# Public_QSGMII_ETHERNET.net
KiCad netlist of a schematic drawn in Altium Designer
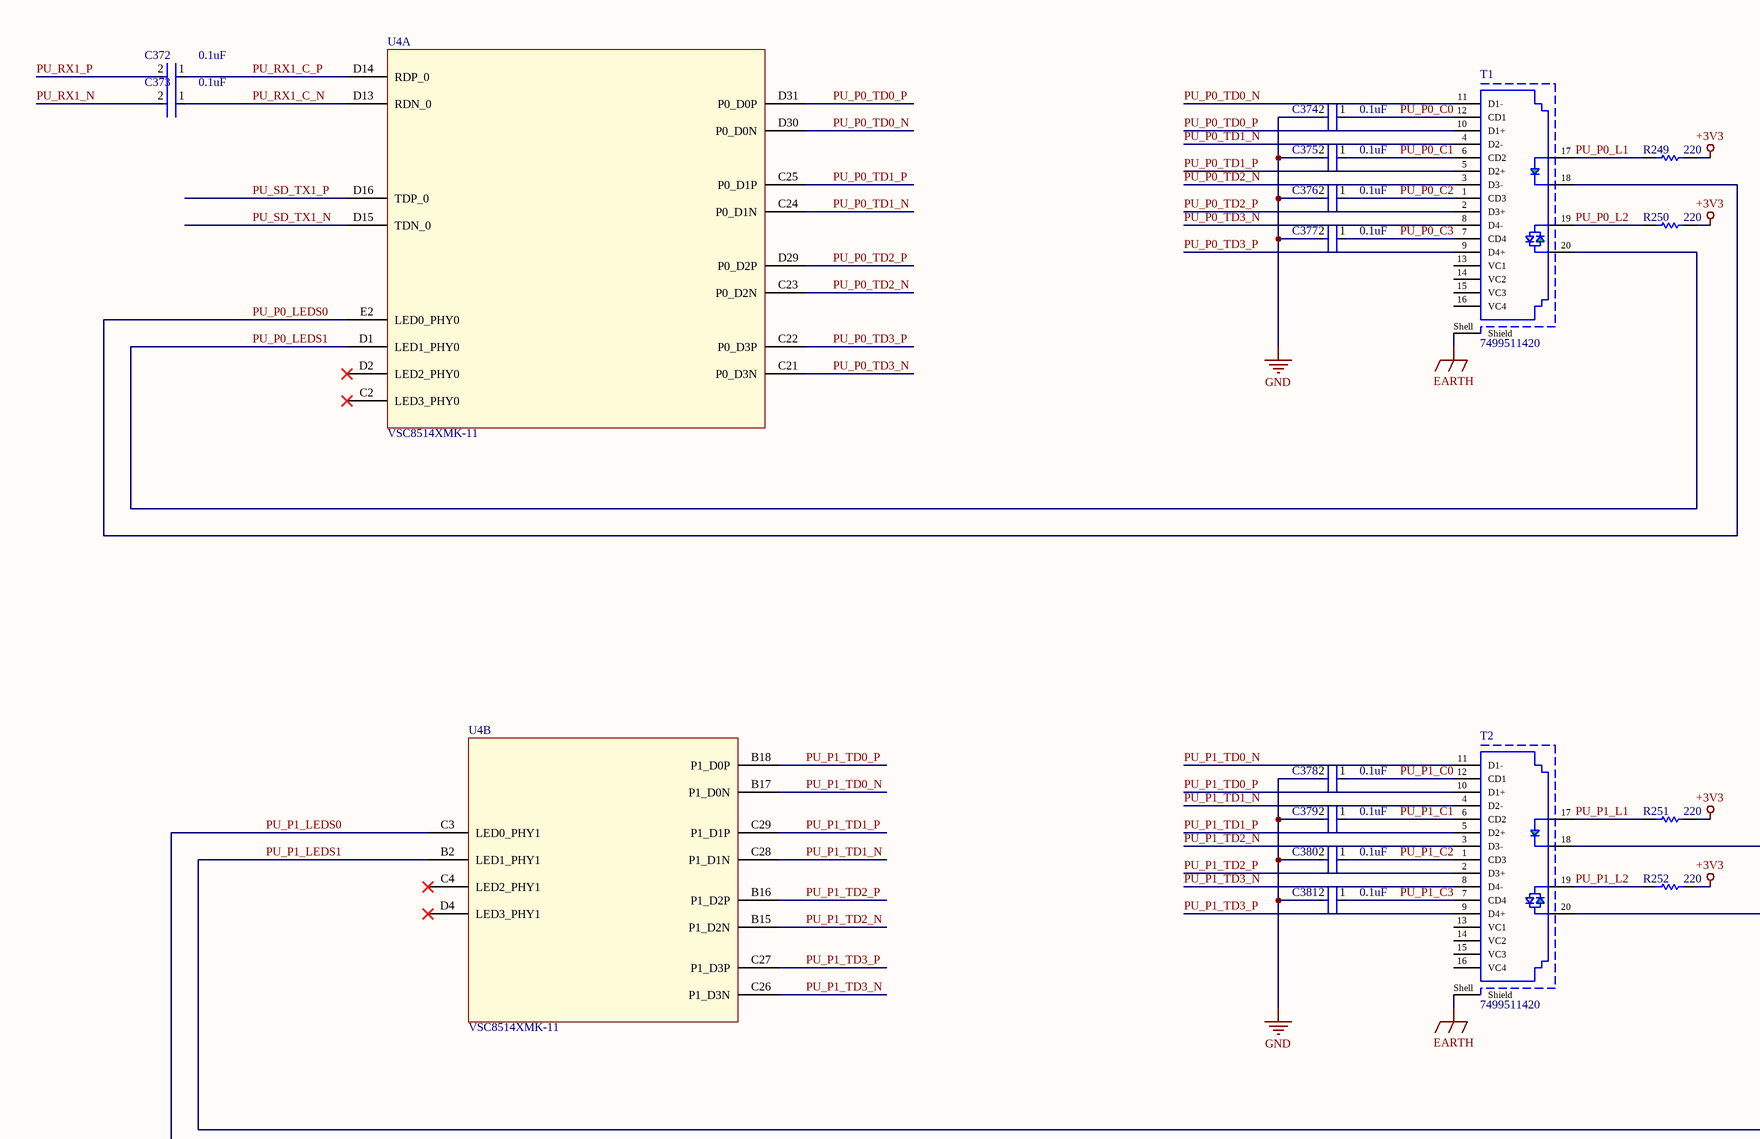
[diagram p0: Public_QSGMII_ETHERNET.SchDoc, top left]
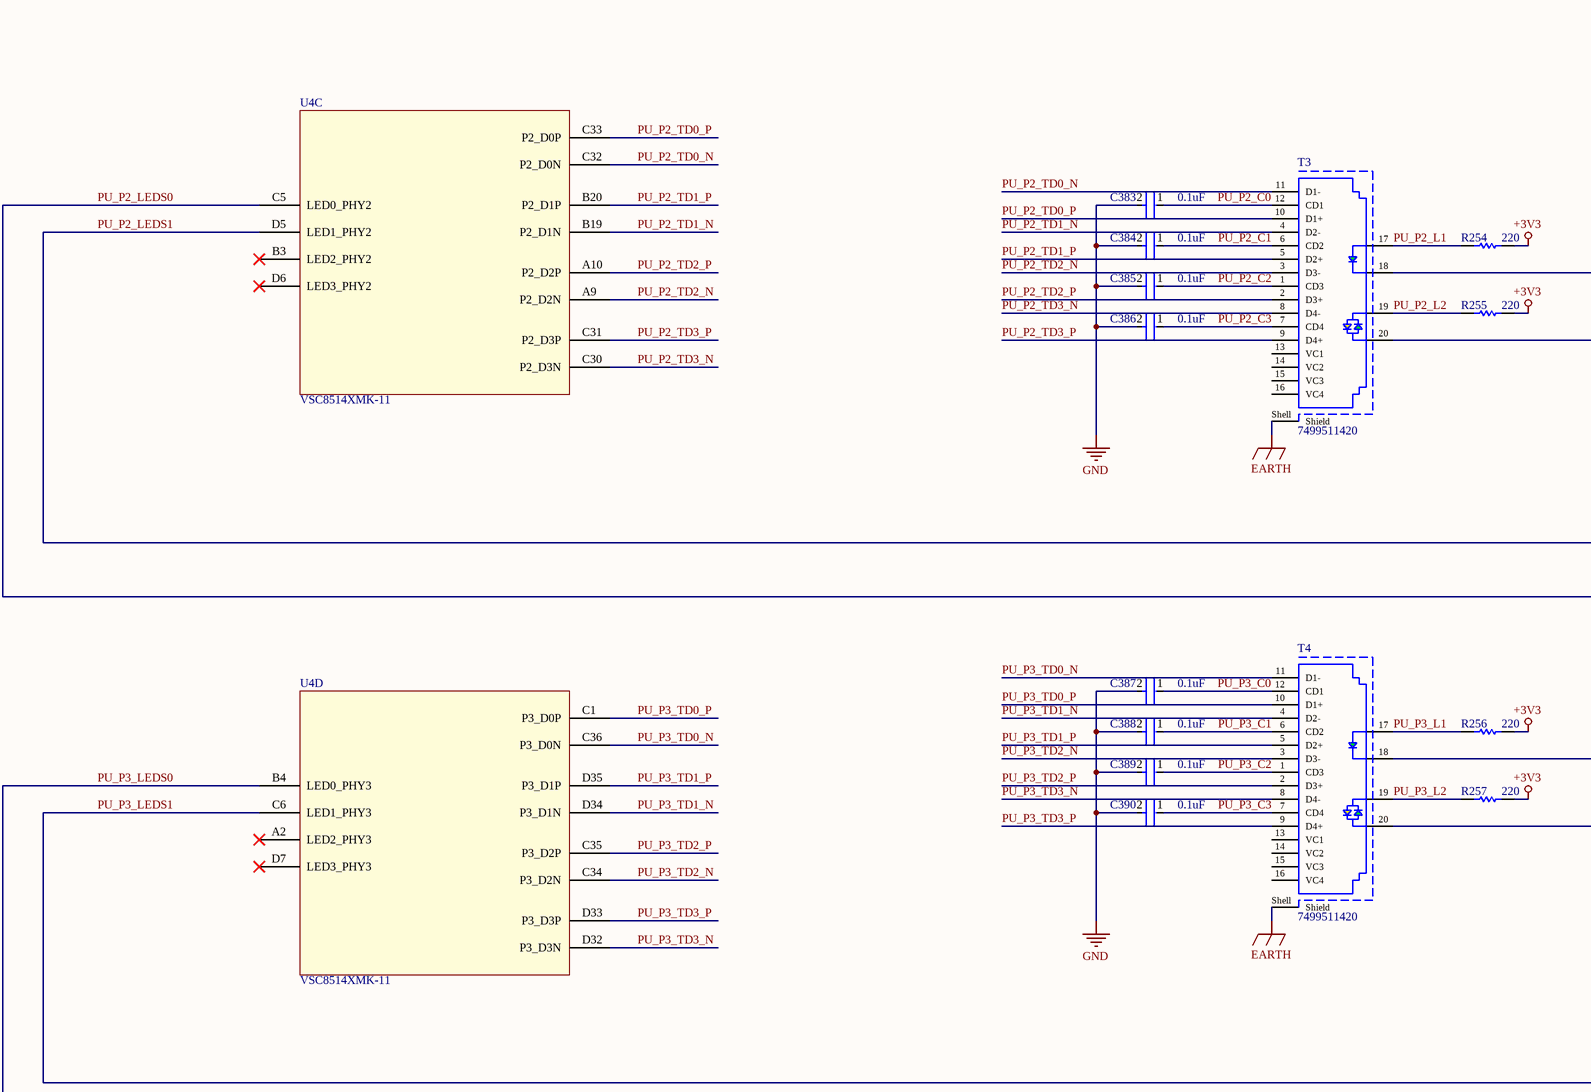
[diagram p1: Public_QSGMII_ETHERNET.SchDoc, bottom left]
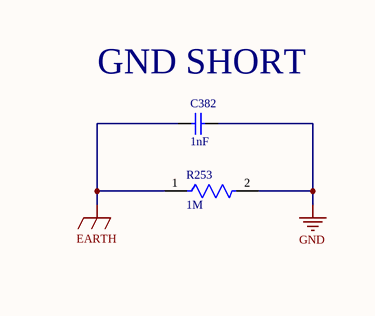
[diagram p2: Public_QSGMII_ETHERNET.SchDoc, bottom right]

(export (version "E")
  (design (tool "Eeschema 10.0.6"))
  (components
    (comp (ref "C372")
      (value "0.1uF")
      (footprint "FP-GRM15-MFG")
      (description "CAP CER 0.1UF 16V X7R 0402")
      (fields (field (name "MANUFACTURER PART NUMBER") "GRM155R71C104KA88D") (field (name "TOLERANCE") "10%"))
      (libsource (lib "Altium Content Vault") (part "236180d848d6139a670b325ea6854c9"))
    )
    (comp (ref "C373")
      (value "0.1uF")
      (footprint "FP-GRM15-MFG")
      (description "CAP CER 0.1UF 16V X7R 0402")
      (fields (field (name "MANUFACTURER PART NUMBER") "GRM155R71C104KA88D") (field (name "TOLERANCE") "10%"))
      (libsource (lib "Altium Content Vault") (part "236180d848d6139a670b325ea6854c9"))
    )
    (comp (ref "C374")
      (value "0.1uF")
      (footprint "FP-GRM15-MFG")
      (description "CAP CER 0.1UF 16V X7R 0402")
      (fields (field (name "MANUFACTURER PART NUMBER") "GRM155R71C104KA88D") (field (name "TOLERANCE") "10%"))
      (libsource (lib "Altium Content Vault") (part "236180d848d6139a670b325ea6854c9"))
    )
    (comp (ref "C375")
      (value "0.1uF")
      (footprint "FP-GRM15-MFG")
      (description "CAP CER 0.1UF 16V X7R 0402")
      (fields (field (name "MANUFACTURER PART NUMBER") "GRM155R71C104KA88D") (field (name "TOLERANCE") "10%"))
      (libsource (lib "Altium Content Vault") (part "236180d848d6139a670b325ea6854c9"))
    )
    (comp (ref "C376")
      (value "0.1uF")
      (footprint "FP-GRM15-MFG")
      (description "CAP CER 0.1UF 16V X7R 0402")
      (fields (field (name "MANUFACTURER PART NUMBER") "GRM155R71C104KA88D") (field (name "TOLERANCE") "10%"))
      (libsource (lib "Altium Content Vault") (part "236180d848d6139a670b325ea6854c9"))
    )
    (comp (ref "C377")
      (value "0.1uF")
      (footprint "FP-GRM15-MFG")
      (description "CAP CER 0.1UF 16V X7R 0402")
      (fields (field (name "MANUFACTURER PART NUMBER") "GRM155R71C104KA88D") (field (name "TOLERANCE") "10%"))
      (libsource (lib "Altium Content Vault") (part "236180d848d6139a670b325ea6854c9"))
    )
    (comp (ref "C378")
      (value "0.1uF")
      (footprint "FP-GRM15-MFG")
      (description "CAP CER 0.1UF 16V X7R 0402")
      (fields (field (name "MANUFACTURER PART NUMBER") "GRM155R71C104KA88D") (field (name "TOLERANCE") "10%"))
      (libsource (lib "Altium Content Vault") (part "236180d848d6139a670b325ea6854c9"))
    )
    (comp (ref "C379")
      (value "0.1uF")
      (footprint "FP-GRM15-MFG")
      (description "CAP CER 0.1UF 16V X7R 0402")
      (fields (field (name "MANUFACTURER PART NUMBER") "GRM155R71C104KA88D") (field (name "TOLERANCE") "10%"))
      (libsource (lib "Altium Content Vault") (part "236180d848d6139a670b325ea6854c9"))
    )
    (comp (ref "C380")
      (value "0.1uF")
      (footprint "FP-GRM15-MFG")
      (description "CAP CER 0.1UF 16V X7R 0402")
      (fields (field (name "MANUFACTURER PART NUMBER") "GRM155R71C104KA88D") (field (name "TOLERANCE") "10%"))
      (libsource (lib "Altium Content Vault") (part "236180d848d6139a670b325ea6854c9"))
    )
    (comp (ref "C381")
      (value "0.1uF")
      (footprint "FP-GRM15-MFG")
      (description "CAP CER 0.1UF 16V X7R 0402")
      (fields (field (name "MANUFACTURER PART NUMBER") "GRM155R71C104KA88D") (field (name "TOLERANCE") "10%"))
      (libsource (lib "Altium Content Vault") (part "236180d848d6139a670b325ea6854c9"))
    )
    (comp (ref "C382")
      (value "1nF")
      (footprint "YAGE-CC1206KKX7R-2_M")
      (description "CAP, Ceramic, 1 nF, 2000 V, 10%, 1206, RoHS, Tape and Reel")
      (fields (field (name "MANUFACTURER") "Yageo") (field (name "TOLERANCE") "±10%"))
      (libsource (lib "Altium Content Vault") (part "CAP-NP-2"))
    )
    (comp (ref "C383")
      (value "0.1uF")
      (footprint "FP-GRM15-MFG")
      (description "CAP CER 0.1UF 16V X7R 0402")
      (fields (field (name "MANUFACTURER PART NUMBER") "GRM155R71C104KA88D") (field (name "TOLERANCE") "10%"))
      (libsource (lib "Altium Content Vault") (part "236180d848d6139a670b325ea6854c9"))
    )
    (comp (ref "C384")
      (value "0.1uF")
      (footprint "FP-GRM15-MFG")
      (description "CAP CER 0.1UF 16V X7R 0402")
      (fields (field (name "MANUFACTURER PART NUMBER") "GRM155R71C104KA88D") (field (name "TOLERANCE") "10%"))
      (libsource (lib "Altium Content Vault") (part "236180d848d6139a670b325ea6854c9"))
    )
    (comp (ref "C385")
      (value "0.1uF")
      (footprint "FP-GRM15-MFG")
      (description "CAP CER 0.1UF 16V X7R 0402")
      (fields (field (name "MANUFACTURER PART NUMBER") "GRM155R71C104KA88D") (field (name "TOLERANCE") "10%"))
      (libsource (lib "Altium Content Vault") (part "236180d848d6139a670b325ea6854c9"))
    )
    (comp (ref "C386")
      (value "0.1uF")
      (footprint "FP-GRM15-MFG")
      (description "CAP CER 0.1UF 16V X7R 0402")
      (fields (field (name "MANUFACTURER PART NUMBER") "GRM155R71C104KA88D") (field (name "TOLERANCE") "10%"))
      (libsource (lib "Altium Content Vault") (part "236180d848d6139a670b325ea6854c9"))
    )
    (comp (ref "C387")
      (value "0.1uF")
      (footprint "FP-GRM15-MFG")
      (description "CAP CER 0.1UF 16V X7R 0402")
      (fields (field (name "MANUFACTURER PART NUMBER") "GRM155R71C104KA88D") (field (name "TOLERANCE") "10%"))
      (libsource (lib "Altium Content Vault") (part "236180d848d6139a670b325ea6854c9"))
    )
    (comp (ref "C388")
      (value "0.1uF")
      (footprint "FP-GRM15-MFG")
      (description "CAP CER 0.1UF 16V X7R 0402")
      (fields (field (name "MANUFACTURER PART NUMBER") "GRM155R71C104KA88D") (field (name "TOLERANCE") "10%"))
      (libsource (lib "Altium Content Vault") (part "236180d848d6139a670b325ea6854c9"))
    )
    (comp (ref "C389")
      (value "0.1uF")
      (footprint "FP-GRM15-MFG")
      (description "CAP CER 0.1UF 16V X7R 0402")
      (fields (field (name "MANUFACTURER PART NUMBER") "GRM155R71C104KA88D") (field (name "TOLERANCE") "10%"))
      (libsource (lib "Altium Content Vault") (part "236180d848d6139a670b325ea6854c9"))
    )
    (comp (ref "C390")
      (value "0.1uF")
      (footprint "FP-GRM15-MFG")
      (description "CAP CER 0.1UF 16V X7R 0402")
      (fields (field (name "MANUFACTURER PART NUMBER") "GRM155R71C104KA88D") (field (name "TOLERANCE") "10%"))
      (libsource (lib "Altium Content Vault") (part "236180d848d6139a670b325ea6854c9"))
    )
    (comp (ref "R249")
      (value "220")
      (footprint "RESC3216X60X45ML10T20")
      (fields (field (name "MANUFACTURER") "Vishay Dale") (field (name "PART NUMBER") "CRCW1206220RFKEA"))
      (libsource (lib "Altium Content Vault") (part "RES"))
    )
    (comp (ref "R250")
      (value "220")
      (footprint "RESC3216X60X45ML10T20")
      (fields (field (name "MANUFACTURER") "Vishay Dale") (field (name "PART NUMBER") "CRCW1206220RFKEA"))
      (libsource (lib "Altium Content Vault") (part "RES"))
    )
    (comp (ref "R251")
      (value "220")
      (footprint "RESC3216X60X45ML10T20")
      (fields (field (name "MANUFACTURER") "Vishay Dale") (field (name "PART NUMBER") "CRCW1206220RFKEA"))
      (libsource (lib "Altium Content Vault") (part "RES"))
    )
    (comp (ref "R252")
      (value "220")
      (footprint "RESC3216X60X45ML10T20")
      (fields (field (name "MANUFACTURER") "Vishay Dale") (field (name "PART NUMBER") "CRCW1206220RFKEA"))
      (libsource (lib "Altium Content Vault") (part "RES"))
    )
    (comp (ref "R253")
      (value "1M")
      (footprint "FP-CRCW2512-e3-IPC_C")
      (description "RES Thick Film, 1Ω, 1%, 1W, 100ppm/°C, 2512")
      (fields (field (name "TOLERANCE") "1%"))
      (libsource (lib "Altium Content Vault") (part "1029c3af85768c4190bb7ad29bc67b5"))
    )
    (comp (ref "R254")
      (value "220")
      (footprint "RESC3216X60X45ML10T20")
      (fields (field (name "MANUFACTURER") "Vishay Dale") (field (name "PART NUMBER") "CRCW1206220RFKEA"))
      (libsource (lib "Altium Content Vault") (part "RES"))
    )
    (comp (ref "R255")
      (value "220")
      (footprint "RESC3216X60X45ML10T20")
      (fields (field (name "MANUFACTURER") "Vishay Dale") (field (name "PART NUMBER") "CRCW1206220RFKEA"))
      (libsource (lib "Altium Content Vault") (part "RES"))
    )
    (comp (ref "R256")
      (value "220")
      (footprint "RESC3216X60X45ML10T20")
      (fields (field (name "MANUFACTURER") "Vishay Dale") (field (name "PART NUMBER") "CRCW1206220RFKEA"))
      (libsource (lib "Altium Content Vault") (part "RES"))
    )
    (comp (ref "R257")
      (value "220")
      (footprint "RESC3216X60X45ML10T20")
      (fields (field (name "MANUFACTURER") "Vishay Dale") (field (name "PART NUMBER") "CRCW1206220RFKEA"))
      (libsource (lib "Altium Content Vault") (part "RES"))
    )
    (comp (ref "T1")
      (value "7499511420")
      (footprint "7499511420")
      (description "WE-RJ45 LAN Transformer, THT, 10/100/1000 Base-T, Port 1x1, Tab Up")
      (fields (field (name "MANUFACTURER") "Wurth Elektronik"))
      (libsource (lib "Altium_WE-RJ45_LAN (rev21a)") (part "7499511420"))
    )
    (comp (ref "T2")
      (value "7499511420")
      (footprint "7499511420")
      (description "WE-RJ45 LAN Transformer, THT, 10/100/1000 Base-T, Port 1x1, Tab Up")
      (fields (field (name "MANUFACTURER") "Wurth Elektronik"))
      (libsource (lib "Altium_WE-RJ45_LAN (rev21a)") (part "7499511420"))
    )
    (comp (ref "T3")
      (value "7499511420")
      (footprint "7499511420")
      (description "WE-RJ45 LAN Transformer, THT, 10/100/1000 Base-T, Port 1x1, Tab Up")
      (fields (field (name "MANUFACTURER") "Wurth Elektronik"))
      (libsource (lib "Altium_WE-RJ45_LAN (rev21a)") (part "7499511420"))
    )
    (comp (ref "T4")
      (value "7499511420")
      (footprint "7499511420")
      (description "WE-RJ45 LAN Transformer, THT, 10/100/1000 Base-T, Port 1x1, Tab Up")
      (fields (field (name "MANUFACTURER") "Wurth Elektronik"))
      (libsource (lib "Altium_WE-RJ45_LAN (rev21a)") (part "7499511420"))
    )
    (comp (ref "U4")
      (value "VSC8514XMK-11")
      (footprint "QFN138_12X12X0P85_MCH")
      (description "No Description Available")
      (fields (field (name "COPYRIGHT") "Copyright (C) 2018 Accelerated Designs. All rights reserved"))
      (libsource (lib "VSC8514XMK-11") (part "VSC8514XMK-11"))
    )
  )
  (nets
    (net (code "1") (name "+3V3") (class "Default")
      (node (ref "R249") (pin "2") (pinfunction "2_2") (pintype "passive"))
      (node (ref "R250") (pin "2") (pinfunction "2_2") (pintype "passive"))
      (node (ref "R251") (pin "2") (pinfunction "2_2") (pintype "passive"))
      (node (ref "R252") (pin "2") (pinfunction "2_2") (pintype "passive"))
      (node (ref "R254") (pin "2") (pinfunction "2_2") (pintype "passive"))
      (node (ref "R255") (pin "2") (pinfunction "2_2") (pintype "passive"))
      (node (ref "R256") (pin "2") (pinfunction "2_2") (pintype "passive"))
      (node (ref "R257") (pin "2") (pinfunction "2_2") (pintype "passive"))
    )
    (net (code "2") (name "/PU_P0_C0") (class "Default")
      (node (ref "C374") (pin "1") (pinfunction "1_1") (pintype "passive"))
      (node (ref "T1") (pin "12") (pinfunction "CD1_12") (pintype "passive"))
    )
    (net (code "3") (name "/PU_P0_C1") (class "Default")
      (node (ref "C375") (pin "1") (pinfunction "1_1") (pintype "passive"))
      (node (ref "T1") (pin "6") (pinfunction "CD2_6") (pintype "passive"))
    )
    (net (code "4") (name "/PU_P0_C2") (class "Default")
      (node (ref "C376") (pin "1") (pinfunction "1_1") (pintype "passive"))
      (node (ref "T1") (pin "1") (pinfunction "CD3_1") (pintype "passive"))
    )
    (net (code "5") (name "/PU_P0_C3") (class "Default")
      (node (ref "C377") (pin "1") (pinfunction "1_1") (pintype "passive"))
      (node (ref "T1") (pin "7") (pinfunction "CD4_7") (pintype "passive"))
    )
    (net (code "6") (name "/PU_P0_L1") (class "Default")
      (node (ref "R249") (pin "1") (pinfunction "1_1") (pintype "passive"))
      (node (ref "T1") (pin "17") (pinfunction "17_17") (pintype "passive"))
    )
    (net (code "7") (name "/PU_P0_L2") (class "Default")
      (node (ref "R250") (pin "1") (pinfunction "1_1") (pintype "passive"))
      (node (ref "T1") (pin "19") (pinfunction "19_19") (pintype "passive"))
    )
    (net (code "8") (name "/PU_P0_LEDS0") (class "Default")
      (node (ref "T1") (pin "18") (pinfunction "18_18") (pintype "passive"))
      (node (ref "U4") (pin "E2") (pinfunction "LED0_PHY0_E2") (pintype "passive"))
    )
    (net (code "9") (name "/PU_P0_LEDS1") (class "Default")
      (node (ref "T1") (pin "20") (pinfunction "20_20") (pintype "passive"))
      (node (ref "U4") (pin "D1") (pinfunction "LED1_PHY0_D1") (pintype "passive"))
    )
    (net (code "10") (name "/PU_P0_TD0_N") (class "Default")
      (node (ref "T1") (pin "11") (pinfunction "D1-_11") (pintype "passive"))
      (node (ref "U4") (pin "D30") (pinfunction "P0_D0N_D30") (pintype "passive"))
    )
    (net (code "11") (name "/PU_P0_TD0_P") (class "Default")
      (node (ref "T1") (pin "10") (pinfunction "D1+_10") (pintype "passive"))
      (node (ref "U4") (pin "D31") (pinfunction "P0_D0P_D31") (pintype "passive"))
    )
    (net (code "12") (name "/PU_P0_TD1_N") (class "Default")
      (node (ref "T1") (pin "4") (pinfunction "D2-_4") (pintype "passive"))
      (node (ref "U4") (pin "C24") (pinfunction "P0_D1N_C24") (pintype "passive"))
    )
    (net (code "13") (name "/PU_P0_TD1_P") (class "Default")
      (node (ref "T1") (pin "5") (pinfunction "D2+_5") (pintype "passive"))
      (node (ref "U4") (pin "C25") (pinfunction "P0_D1P_C25") (pintype "passive"))
    )
    (net (code "14") (name "/PU_P0_TD2_N") (class "Default")
      (node (ref "T1") (pin "3") (pinfunction "D3-_3") (pintype "passive"))
      (node (ref "U4") (pin "C23") (pinfunction "P0_D2N_C23") (pintype "passive"))
    )
    (net (code "15") (name "/PU_P0_TD2_P") (class "Default")
      (node (ref "T1") (pin "2") (pinfunction "D3+_2") (pintype "passive"))
      (node (ref "U4") (pin "D29") (pinfunction "P0_D2P_D29") (pintype "passive"))
    )
    (net (code "16") (name "/PU_P0_TD3_N") (class "Default")
      (node (ref "T1") (pin "8") (pinfunction "D4-_8") (pintype "passive"))
      (node (ref "U4") (pin "C21") (pinfunction "P0_D3N_C21") (pintype "passive"))
    )
    (net (code "17") (name "/PU_P0_TD3_P") (class "Default")
      (node (ref "T1") (pin "9") (pinfunction "D4+_9") (pintype "passive"))
      (node (ref "U4") (pin "C22") (pinfunction "P0_D3P_C22") (pintype "passive"))
    )
    (net (code "18") (name "/PU_P1_C0") (class "Default")
      (node (ref "C378") (pin "1") (pinfunction "1_1") (pintype "passive"))
      (node (ref "T2") (pin "12") (pinfunction "CD1_12") (pintype "passive"))
    )
    (net (code "19") (name "/PU_P1_C1") (class "Default")
      (node (ref "C379") (pin "1") (pinfunction "1_1") (pintype "passive"))
      (node (ref "T2") (pin "6") (pinfunction "CD2_6") (pintype "passive"))
    )
    (net (code "20") (name "/PU_P1_C2") (class "Default")
      (node (ref "C380") (pin "1") (pinfunction "1_1") (pintype "passive"))
      (node (ref "T2") (pin "1") (pinfunction "CD3_1") (pintype "passive"))
    )
    (net (code "21") (name "/PU_P1_C3") (class "Default")
      (node (ref "C381") (pin "1") (pinfunction "1_1") (pintype "passive"))
      (node (ref "T2") (pin "7") (pinfunction "CD4_7") (pintype "passive"))
    )
    (net (code "22") (name "/PU_P1_L1") (class "Default")
      (node (ref "R251") (pin "1") (pinfunction "1_1") (pintype "passive"))
      (node (ref "T2") (pin "17") (pinfunction "17_17") (pintype "passive"))
    )
    (net (code "23") (name "/PU_P1_L2") (class "Default")
      (node (ref "R252") (pin "1") (pinfunction "1_1") (pintype "passive"))
      (node (ref "T2") (pin "19") (pinfunction "19_19") (pintype "passive"))
    )
    (net (code "24") (name "/PU_P1_LEDS0") (class "Default")
      (node (ref "T2") (pin "18") (pinfunction "18_18") (pintype "passive"))
      (node (ref "U4") (pin "C3") (pinfunction "LED0_PHY1_C3") (pintype "passive"))
    )
    (net (code "25") (name "/PU_P1_LEDS1") (class "Default")
      (node (ref "T2") (pin "20") (pinfunction "20_20") (pintype "passive"))
      (node (ref "U4") (pin "B2") (pinfunction "LED1_PHY1_B2") (pintype "passive"))
    )
    (net (code "26") (name "/PU_P1_TD0_N") (class "Default")
      (node (ref "T2") (pin "11") (pinfunction "D1-_11") (pintype "passive"))
      (node (ref "U4") (pin "B17") (pinfunction "P1_D0N_B17") (pintype "passive"))
    )
    (net (code "27") (name "/PU_P1_TD0_P") (class "Default")
      (node (ref "T2") (pin "10") (pinfunction "D1+_10") (pintype "passive"))
      (node (ref "U4") (pin "B18") (pinfunction "P1_D0P_B18") (pintype "passive"))
    )
    (net (code "28") (name "/PU_P1_TD1_N") (class "Default")
      (node (ref "T2") (pin "4") (pinfunction "D2-_4") (pintype "passive"))
      (node (ref "U4") (pin "C28") (pinfunction "P1_D1N_C28") (pintype "passive"))
    )
    (net (code "29") (name "/PU_P1_TD1_P") (class "Default")
      (node (ref "T2") (pin "5") (pinfunction "D2+_5") (pintype "passive"))
      (node (ref "U4") (pin "C29") (pinfunction "P1_D1P_C29") (pintype "passive"))
    )
    (net (code "30") (name "/PU_P1_TD2_N") (class "Default")
      (node (ref "T2") (pin "3") (pinfunction "D3-_3") (pintype "passive"))
      (node (ref "U4") (pin "B15") (pinfunction "P1_D2N_B15") (pintype "passive"))
    )
    (net (code "31") (name "/PU_P1_TD2_P") (class "Default")
      (node (ref "T2") (pin "2") (pinfunction "D3+_2") (pintype "passive"))
      (node (ref "U4") (pin "B16") (pinfunction "P1_D2P_B16") (pintype "passive"))
    )
    (net (code "32") (name "/PU_P1_TD3_N") (class "Default")
      (node (ref "T2") (pin "8") (pinfunction "D4-_8") (pintype "passive"))
      (node (ref "U4") (pin "C26") (pinfunction "P1_D3N_C26") (pintype "passive"))
    )
    (net (code "33") (name "/PU_P1_TD3_P") (class "Default")
      (node (ref "T2") (pin "9") (pinfunction "D4+_9") (pintype "passive"))
      (node (ref "U4") (pin "C27") (pinfunction "P1_D3P_C27") (pintype "passive"))
    )
    (net (code "34") (name "/PU_P2_C0") (class "Default")
      (node (ref "C383") (pin "1") (pinfunction "1_1") (pintype "passive"))
      (node (ref "T3") (pin "12") (pinfunction "CD1_12") (pintype "passive"))
    )
    (net (code "35") (name "/PU_P2_C1") (class "Default")
      (node (ref "C384") (pin "1") (pinfunction "1_1") (pintype "passive"))
      (node (ref "T3") (pin "6") (pinfunction "CD2_6") (pintype "passive"))
    )
    (net (code "36") (name "/PU_P2_C2") (class "Default")
      (node (ref "C385") (pin "1") (pinfunction "1_1") (pintype "passive"))
      (node (ref "T3") (pin "1") (pinfunction "CD3_1") (pintype "passive"))
    )
    (net (code "37") (name "/PU_P2_C3") (class "Default")
      (node (ref "C386") (pin "1") (pinfunction "1_1") (pintype "passive"))
      (node (ref "T3") (pin "7") (pinfunction "CD4_7") (pintype "passive"))
    )
    (net (code "38") (name "/PU_P2_L1") (class "Default")
      (node (ref "R254") (pin "1") (pinfunction "1_1") (pintype "passive"))
      (node (ref "T3") (pin "17") (pinfunction "17_17") (pintype "passive"))
    )
    (net (code "39") (name "/PU_P2_L2") (class "Default")
      (node (ref "R255") (pin "1") (pinfunction "1_1") (pintype "passive"))
      (node (ref "T3") (pin "19") (pinfunction "19_19") (pintype "passive"))
    )
    (net (code "40") (name "/PU_P2_LEDS0") (class "Default")
      (node (ref "T3") (pin "18") (pinfunction "18_18") (pintype "passive"))
      (node (ref "U4") (pin "C5") (pinfunction "LED0_PHY2_C5") (pintype "passive"))
    )
    (net (code "41") (name "/PU_P2_LEDS1") (class "Default")
      (node (ref "T3") (pin "20") (pinfunction "20_20") (pintype "passive"))
      (node (ref "U4") (pin "D5") (pinfunction "LED1_PHY2_D5") (pintype "passive"))
    )
    (net (code "42") (name "/PU_P2_TD0_N") (class "Default")
      (node (ref "T3") (pin "11") (pinfunction "D1-_11") (pintype "passive"))
      (node (ref "U4") (pin "C32") (pinfunction "P2_D0N_C32") (pintype "passive"))
    )
    (net (code "43") (name "/PU_P2_TD0_P") (class "Default")
      (node (ref "T3") (pin "10") (pinfunction "D1+_10") (pintype "passive"))
      (node (ref "U4") (pin "C33") (pinfunction "P2_D0P_C33") (pintype "passive"))
    )
    (net (code "44") (name "/PU_P2_TD1_N") (class "Default")
      (node (ref "T3") (pin "4") (pinfunction "D2-_4") (pintype "passive"))
      (node (ref "U4") (pin "B19") (pinfunction "P2_D1N_B19") (pintype "passive"))
    )
    (net (code "45") (name "/PU_P2_TD1_P") (class "Default")
      (node (ref "T3") (pin "5") (pinfunction "D2+_5") (pintype "passive"))
      (node (ref "U4") (pin "B20") (pinfunction "P2_D1P_B20") (pintype "passive"))
    )
    (net (code "46") (name "/PU_P2_TD2_N") (class "Default")
      (node (ref "T3") (pin "3") (pinfunction "D3-_3") (pintype "passive"))
      (node (ref "U4") (pin "A9") (pinfunction "P2_D2N_A9") (pintype "passive"))
    )
    (net (code "47") (name "/PU_P2_TD2_P") (class "Default")
      (node (ref "T3") (pin "2") (pinfunction "D3+_2") (pintype "passive"))
      (node (ref "U4") (pin "A10") (pinfunction "P2_D2P_A10") (pintype "passive"))
    )
    (net (code "48") (name "/PU_P2_TD3_N") (class "Default")
      (node (ref "T3") (pin "8") (pinfunction "D4-_8") (pintype "passive"))
      (node (ref "U4") (pin "C30") (pinfunction "P2_D3N_C30") (pintype "passive"))
    )
    (net (code "49") (name "/PU_P2_TD3_P") (class "Default")
      (node (ref "T3") (pin "9") (pinfunction "D4+_9") (pintype "passive"))
      (node (ref "U4") (pin "C31") (pinfunction "P2_D3P_C31") (pintype "passive"))
    )
    (net (code "50") (name "/PU_P3_C0") (class "Default")
      (node (ref "C387") (pin "1") (pinfunction "1_1") (pintype "passive"))
      (node (ref "T4") (pin "12") (pinfunction "CD1_12") (pintype "passive"))
    )
    (net (code "51") (name "/PU_P3_C1") (class "Default")
      (node (ref "C388") (pin "1") (pinfunction "1_1") (pintype "passive"))
      (node (ref "T4") (pin "6") (pinfunction "CD2_6") (pintype "passive"))
    )
    (net (code "52") (name "/PU_P3_C2") (class "Default")
      (node (ref "C389") (pin "1") (pinfunction "1_1") (pintype "passive"))
      (node (ref "T4") (pin "1") (pinfunction "CD3_1") (pintype "passive"))
    )
    (net (code "53") (name "/PU_P3_C3") (class "Default")
      (node (ref "C390") (pin "1") (pinfunction "1_1") (pintype "passive"))
      (node (ref "T4") (pin "7") (pinfunction "CD4_7") (pintype "passive"))
    )
    (net (code "54") (name "/PU_P3_L1") (class "Default")
      (node (ref "R256") (pin "1") (pinfunction "1_1") (pintype "passive"))
      (node (ref "T4") (pin "17") (pinfunction "17_17") (pintype "passive"))
    )
    (net (code "55") (name "/PU_P3_L2") (class "Default")
      (node (ref "R257") (pin "1") (pinfunction "1_1") (pintype "passive"))
      (node (ref "T4") (pin "19") (pinfunction "19_19") (pintype "passive"))
    )
    (net (code "56") (name "/PU_P3_LEDS0") (class "Default")
      (node (ref "T4") (pin "18") (pinfunction "18_18") (pintype "passive"))
      (node (ref "U4") (pin "B4") (pinfunction "LED0_PHY3_B4") (pintype "passive"))
    )
    (net (code "57") (name "/PU_P3_LEDS1") (class "Default")
      (node (ref "T4") (pin "20") (pinfunction "20_20") (pintype "passive"))
      (node (ref "U4") (pin "C6") (pinfunction "LED1_PHY3_C6") (pintype "passive"))
    )
    (net (code "58") (name "/PU_P3_TD0_N") (class "Default")
      (node (ref "T4") (pin "11") (pinfunction "D1-_11") (pintype "passive"))
      (node (ref "U4") (pin "C36") (pinfunction "P3_D0N_C36") (pintype "passive"))
    )
    (net (code "59") (name "/PU_P3_TD0_P") (class "Default")
      (node (ref "T4") (pin "10") (pinfunction "D1+_10") (pintype "passive"))
      (node (ref "U4") (pin "C1") (pinfunction "P3_D0P_C1") (pintype "passive"))
    )
    (net (code "60") (name "/PU_P3_TD1_N") (class "Default")
      (node (ref "T4") (pin "4") (pinfunction "D2-_4") (pintype "passive"))
      (node (ref "U4") (pin "D34") (pinfunction "P3_D1N_D34") (pintype "passive"))
    )
    (net (code "61") (name "/PU_P3_TD1_P") (class "Default")
      (node (ref "T4") (pin "5") (pinfunction "D2+_5") (pintype "passive"))
      (node (ref "U4") (pin "D35") (pinfunction "P3_D1P_D35") (pintype "passive"))
    )
    (net (code "62") (name "/PU_P3_TD2_N") (class "Default")
      (node (ref "T4") (pin "3") (pinfunction "D3-_3") (pintype "passive"))
      (node (ref "U4") (pin "C34") (pinfunction "P3_D2N_C34") (pintype "passive"))
    )
    (net (code "63") (name "/PU_P3_TD2_P") (class "Default")
      (node (ref "T4") (pin "2") (pinfunction "D3+_2") (pintype "passive"))
      (node (ref "U4") (pin "C35") (pinfunction "P3_D2P_C35") (pintype "passive"))
    )
    (net (code "64") (name "/PU_P3_TD3_N") (class "Default")
      (node (ref "T4") (pin "8") (pinfunction "D4-_8") (pintype "passive"))
      (node (ref "U4") (pin "D32") (pinfunction "P3_D3N_D32") (pintype "passive"))
    )
    (net (code "65") (name "/PU_P3_TD3_P") (class "Default")
      (node (ref "T4") (pin "9") (pinfunction "D4+_9") (pintype "passive"))
      (node (ref "U4") (pin "D33") (pinfunction "P3_D3P_D33") (pintype "passive"))
    )
    (net (code "66") (name "/PU_RX1_C_N") (class "Default")
      (node (ref "C373") (pin "1") (pinfunction "1_1") (pintype "passive"))
      (node (ref "U4") (pin "D13") (pinfunction "RDN_0_D13") (pintype "passive"))
    )
    (net (code "67") (name "/PU_RX1_C_P") (class "Default")
      (node (ref "C372") (pin "1") (pinfunction "1_1") (pintype "passive"))
      (node (ref "U4") (pin "D14") (pinfunction "RDP_0_D14") (pintype "passive"))
    )
    (net (code "68") (name "/PU_RX1_N") (class "Default")
      (node (ref "C373") (pin "2") (pinfunction "2_2") (pintype "passive"))
    )
    (net (code "69") (name "/PU_RX1_P") (class "Default")
      (node (ref "C372") (pin "2") (pinfunction "2_2") (pintype "passive"))
    )
    (net (code "70") (name "/PU_SD_TX1_N") (class "Default")
      (node (ref "U4") (pin "D15") (pinfunction "TDN_0_D15") (pintype "passive"))
    )
    (net (code "71") (name "/PU_SD_TX1_P") (class "Default")
      (node (ref "U4") (pin "D16") (pinfunction "TDP_0_D16") (pintype "passive"))
    )
    (net (code "72") (name "EARTH") (class "Default")
      (node (ref "C382") (pin "1") (pinfunction "1_1") (pintype "passive"))
      (node (ref "R253") (pin "1") (pinfunction "1_1") (pintype "passive"))
      (node (ref "T1") (pin "Shell") (pinfunction "Shield_Shell") (pintype "passive"))
      (node (ref "T2") (pin "Shell") (pinfunction "Shield_Shell") (pintype "passive"))
      (node (ref "T3") (pin "Shell") (pinfunction "Shield_Shell") (pintype "passive"))
      (node (ref "T4") (pin "Shell") (pinfunction "Shield_Shell") (pintype "passive"))
    )
    (net (code "73") (name "GND") (class "Default")
      (node (ref "C374") (pin "2") (pinfunction "2_2") (pintype "passive"))
      (node (ref "C375") (pin "2") (pinfunction "2_2") (pintype "passive"))
      (node (ref "C376") (pin "2") (pinfunction "2_2") (pintype "passive"))
      (node (ref "C377") (pin "2") (pinfunction "2_2") (pintype "passive"))
      (node (ref "C378") (pin "2") (pinfunction "2_2") (pintype "passive"))
      (node (ref "C379") (pin "2") (pinfunction "2_2") (pintype "passive"))
      (node (ref "C380") (pin "2") (pinfunction "2_2") (pintype "passive"))
      (node (ref "C381") (pin "2") (pinfunction "2_2") (pintype "passive"))
      (node (ref "C382") (pin "2") (pinfunction "2_2") (pintype "passive"))
      (node (ref "C383") (pin "2") (pinfunction "2_2") (pintype "passive"))
      (node (ref "C384") (pin "2") (pinfunction "2_2") (pintype "passive"))
      (node (ref "C385") (pin "2") (pinfunction "2_2") (pintype "passive"))
      (node (ref "C386") (pin "2") (pinfunction "2_2") (pintype "passive"))
      (node (ref "C387") (pin "2") (pinfunction "2_2") (pintype "passive"))
      (node (ref "C388") (pin "2") (pinfunction "2_2") (pintype "passive"))
      (node (ref "C389") (pin "2") (pinfunction "2_2") (pintype "passive"))
      (node (ref "C390") (pin "2") (pinfunction "2_2") (pintype "passive"))
      (node (ref "R253") (pin "2") (pinfunction "2_2") (pintype "passive"))
    )
    (net (code "74") (name "unconnected-(T1-VC1-Pad13)") (class "Default")
      (node (ref "T1") (pin "13") (pinfunction "VC1_13") (pintype "passive"))
    )
    (net (code "75") (name "unconnected-(T1-VC2-Pad14)") (class "Default")
      (node (ref "T1") (pin "14") (pinfunction "VC2_14") (pintype "passive"))
    )
    (net (code "76") (name "unconnected-(T1-VC3-Pad15)") (class "Default")
      (node (ref "T1") (pin "15") (pinfunction "VC3_15") (pintype "passive"))
    )
    (net (code "77") (name "unconnected-(T1-VC4-Pad16)") (class "Default")
      (node (ref "T1") (pin "16") (pinfunction "VC4_16") (pintype "passive"))
    )
    (net (code "78") (name "unconnected-(T2-VC1-Pad13)") (class "Default")
      (node (ref "T2") (pin "13") (pinfunction "VC1_13") (pintype "passive"))
    )
    (net (code "79") (name "unconnected-(T2-VC2-Pad14)") (class "Default")
      (node (ref "T2") (pin "14") (pinfunction "VC2_14") (pintype "passive"))
    )
    (net (code "80") (name "unconnected-(T2-VC3-Pad15)") (class "Default")
      (node (ref "T2") (pin "15") (pinfunction "VC3_15") (pintype "passive"))
    )
    (net (code "81") (name "unconnected-(T2-VC4-Pad16)") (class "Default")
      (node (ref "T2") (pin "16") (pinfunction "VC4_16") (pintype "passive"))
    )
    (net (code "82") (name "unconnected-(T3-VC1-Pad13)") (class "Default")
      (node (ref "T3") (pin "13") (pinfunction "VC1_13") (pintype "passive"))
    )
    (net (code "83") (name "unconnected-(T3-VC2-Pad14)") (class "Default")
      (node (ref "T3") (pin "14") (pinfunction "VC2_14") (pintype "passive"))
    )
    (net (code "84") (name "unconnected-(T3-VC3-Pad15)") (class "Default")
      (node (ref "T3") (pin "15") (pinfunction "VC3_15") (pintype "passive"))
    )
    (net (code "85") (name "unconnected-(T3-VC4-Pad16)") (class "Default")
      (node (ref "T3") (pin "16") (pinfunction "VC4_16") (pintype "passive"))
    )
    (net (code "86") (name "unconnected-(T4-VC1-Pad13)") (class "Default")
      (node (ref "T4") (pin "13") (pinfunction "VC1_13") (pintype "passive"))
    )
    (net (code "87") (name "unconnected-(T4-VC2-Pad14)") (class "Default")
      (node (ref "T4") (pin "14") (pinfunction "VC2_14") (pintype "passive"))
    )
    (net (code "88") (name "unconnected-(T4-VC3-Pad15)") (class "Default")
      (node (ref "T4") (pin "15") (pinfunction "VC3_15") (pintype "passive"))
    )
    (net (code "89") (name "unconnected-(T4-VC4-Pad16)") (class "Default")
      (node (ref "T4") (pin "16") (pinfunction "VC4_16") (pintype "passive"))
    )
    (net (code "90") (name "unconnected-(U4A-LED2_PHY0-PadD2)") (class "Default")
      (node (ref "U4") (pin "D2") (pinfunction "LED2_PHY0_D2") (pintype "passive+no_connect"))
    )
    (net (code "91") (name "unconnected-(U4A-LED3_PHY0-PadC2)") (class "Default")
      (node (ref "U4") (pin "C2") (pinfunction "LED3_PHY0_C2") (pintype "passive+no_connect"))
    )
    (net (code "92") (name "unconnected-(U4B-LED2_PHY1-PadC4)") (class "Default")
      (node (ref "U4") (pin "C4") (pinfunction "LED2_PHY1_C4") (pintype "passive+no_connect"))
    )
    (net (code "93") (name "unconnected-(U4B-LED3_PHY1-PadD4)") (class "Default")
      (node (ref "U4") (pin "D4") (pinfunction "LED3_PHY1_D4") (pintype "passive+no_connect"))
    )
    (net (code "94") (name "unconnected-(U4C-LED2_PHY2-PadB3)") (class "Default")
      (node (ref "U4") (pin "B3") (pinfunction "LED2_PHY2_B3") (pintype "passive+no_connect"))
    )
    (net (code "95") (name "unconnected-(U4C-LED3_PHY2-PadD6)") (class "Default")
      (node (ref "U4") (pin "D6") (pinfunction "LED3_PHY2_D6") (pintype "passive+no_connect"))
    )
    (net (code "96") (name "unconnected-(U4D-LED2_PHY3-PadA2)") (class "Default")
      (node (ref "U4") (pin "A2") (pinfunction "LED2_PHY3_A2") (pintype "passive+no_connect"))
    )
    (net (code "97") (name "unconnected-(U4D-LED3_PHY3-PadD7)") (class "Default")
      (node (ref "U4") (pin "D7") (pinfunction "LED3_PHY3_D7") (pintype "passive+no_connect"))
    )
  )
)
